# MCU_ADC.net
KiCad netlist of a schematic drawn in Altium Designer
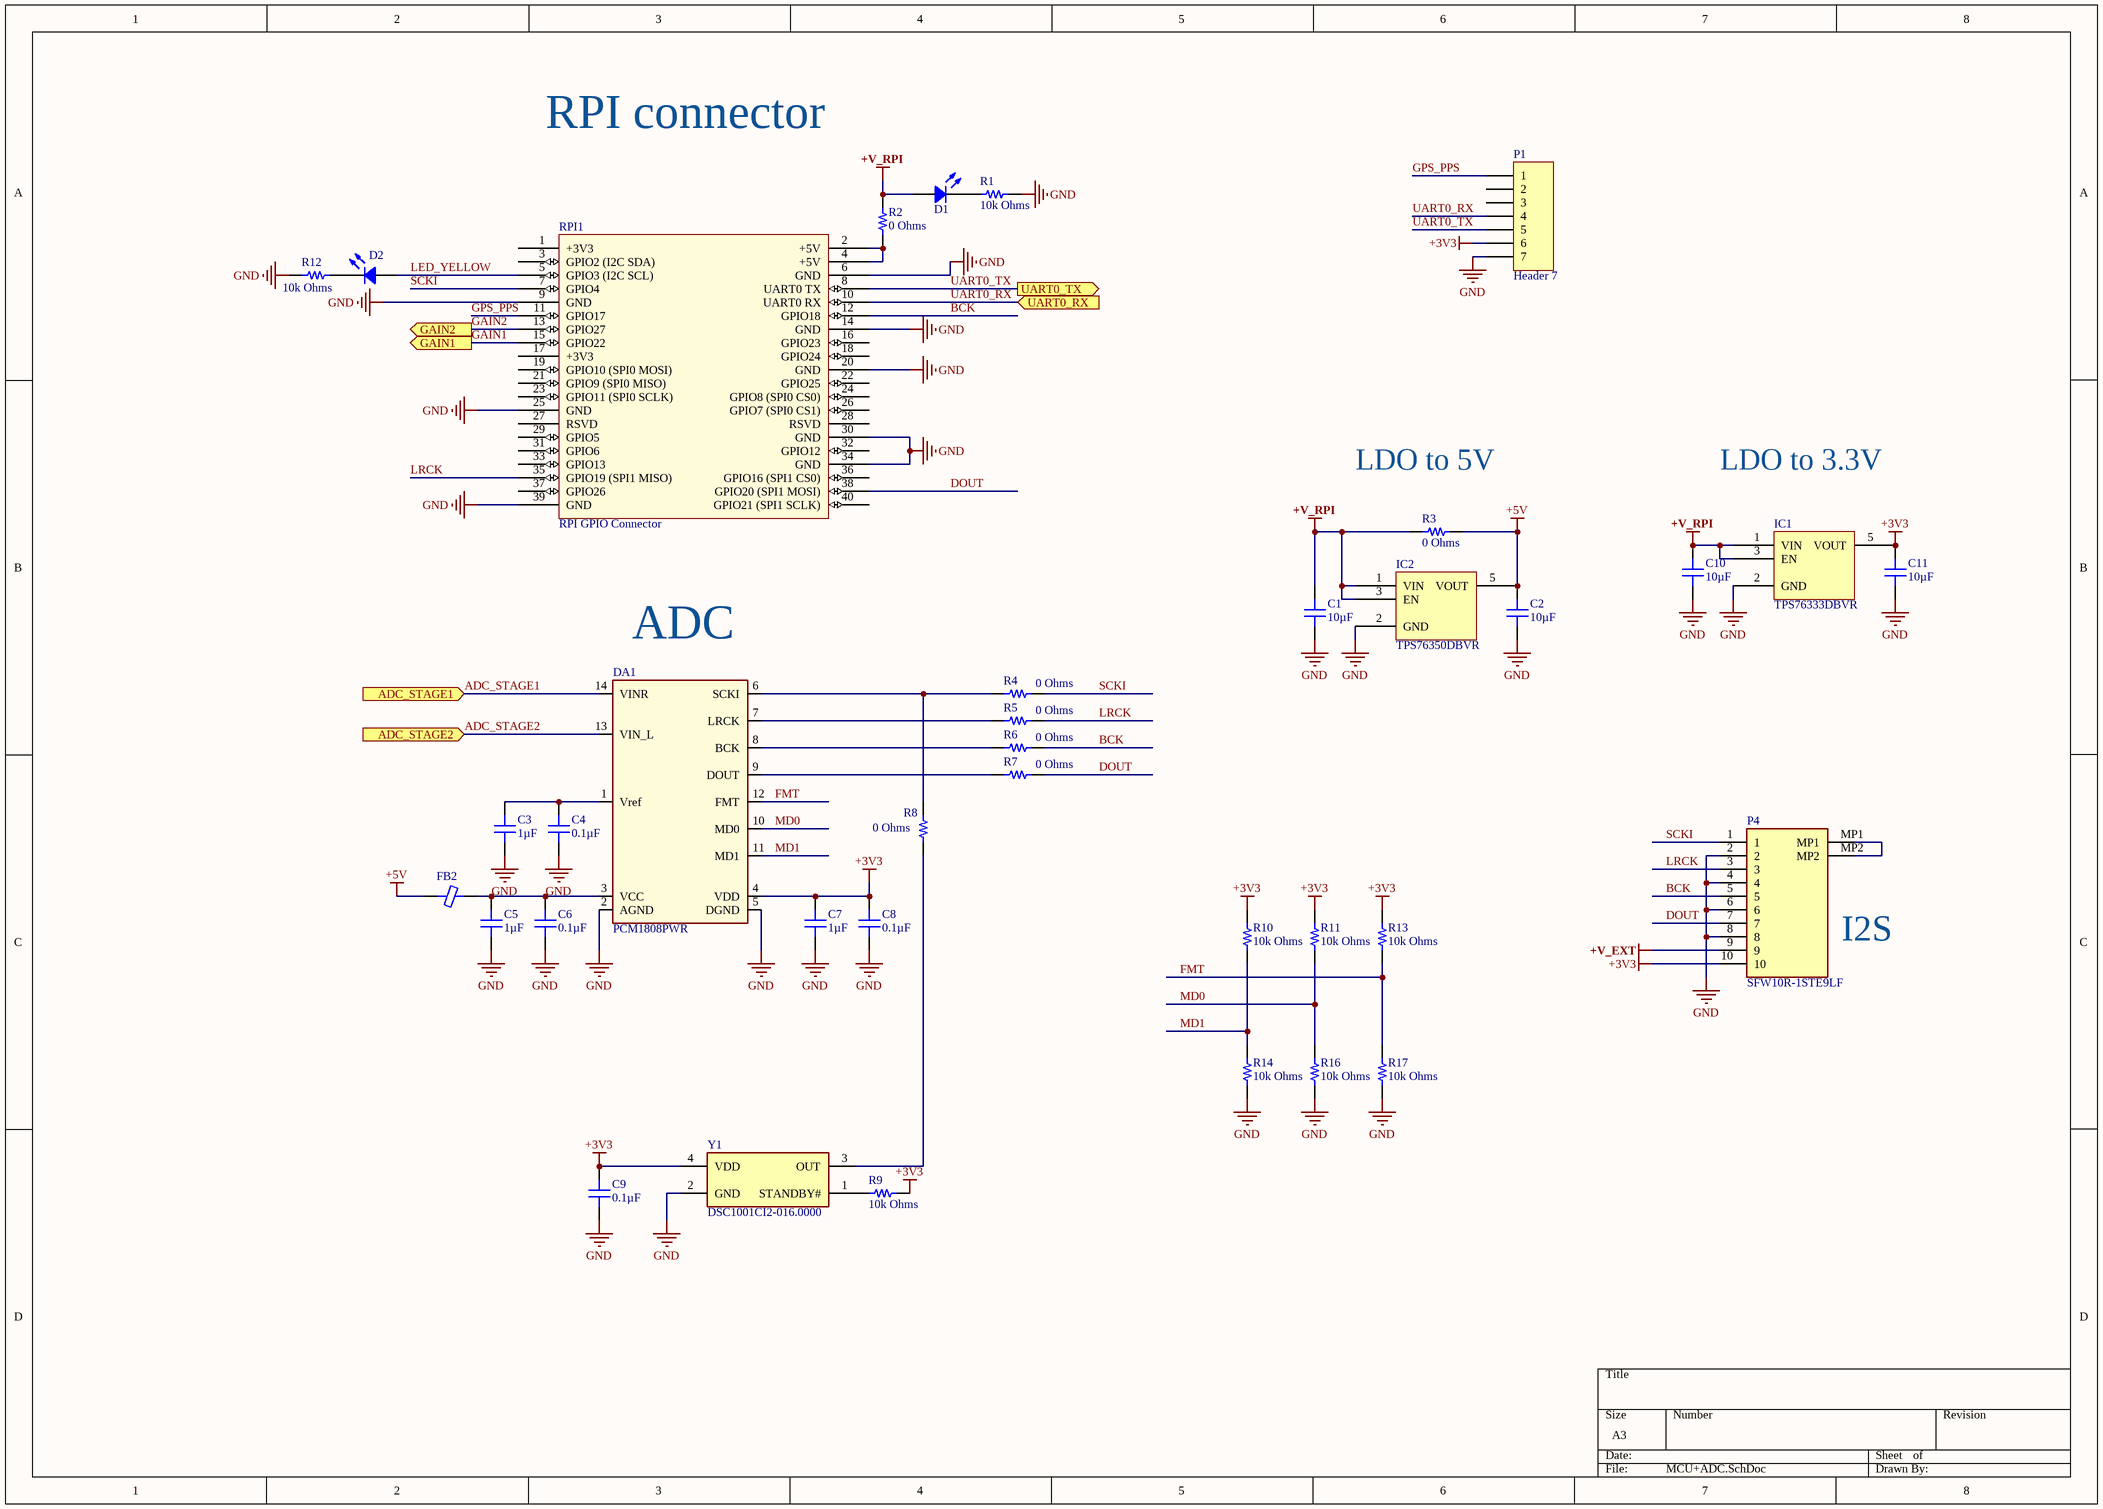
[diagram p0: MCU+ADC.SchDoc]

(export (version "E")
  (design (tool "Eeschema 10.0.6"))
  (components
    (comp (ref "C1")
      (value "10µF")
      (footprint "CAP 0603_1608")
      (description "CAP CER 0.1UF 10V X7R 0603")
      (fields (field (name "PART NUMBER") "100X14W104MV4T"))
      (libsource (lib "Celestial Altium Library - altium_library") (part "Capacitor"))
    )
    (comp (ref "C2")
      (value "10µF")
      (footprint "CAP 0603_1608")
      (description "CAP CER 0.1UF 10V X7R 0603")
      (fields (field (name "PART NUMBER") "100X14W104MV4T"))
      (libsource (lib "Celestial Altium Library - altium_library") (part "Capacitor"))
    )
    (comp (ref "C3")
      (value "1µF")
      (footprint "CAP 0603_1608")
      (description "CAP CER 0.1UF 10V X7R 0603")
      (fields (field (name "PART NUMBER") "100X14W104MV4T"))
      (libsource (lib "Celestial Altium Library - altium_library") (part "Capacitor"))
    )
    (comp (ref "C4")
      (value "0.1µF")
      (footprint "CAP 0603_1608")
      (description "CAP CER 0.1UF 10V X7R 0603")
      (fields (field (name "PART NUMBER") "100X14W104MV4T"))
      (libsource (lib "Celestial Altium Library - altium_library") (part "Capacitor"))
    )
    (comp (ref "C5")
      (value "1µF")
      (footprint "CAP 0603_1608")
      (description "CAP CER 0.1UF 10V X7R 0603")
      (fields (field (name "PART NUMBER") "100X14W104MV4T"))
      (libsource (lib "Celestial Altium Library - altium_library") (part "Capacitor"))
    )
    (comp (ref "C6")
      (value "0.1µF")
      (footprint "CAP 0603_1608")
      (description "CAP CER 0.1UF 10V X7R 0603")
      (fields (field (name "PART NUMBER") "100X14W104MV4T"))
      (libsource (lib "Celestial Altium Library - altium_library") (part "Capacitor"))
    )
    (comp (ref "C7")
      (value "1µF")
      (footprint "CAP 0603_1608")
      (description "CAP CER 0.1UF 10V X7R 0603")
      (fields (field (name "PART NUMBER") "100X14W104MV4T"))
      (libsource (lib "Celestial Altium Library - altium_library") (part "Capacitor"))
    )
    (comp (ref "C8")
      (value "0.1µF")
      (footprint "CAP 0603_1608")
      (description "CAP CER 0.1UF 10V X7R 0603")
      (fields (field (name "PART NUMBER") "100X14W104MV4T"))
      (libsource (lib "Celestial Altium Library - altium_library") (part "Capacitor"))
    )
    (comp (ref "C9")
      (value "0.1µF")
      (footprint "CAP 0603_1608")
      (description "CAP CER 0.1UF 10V X7R 0603")
      (fields (field (name "PART NUMBER") "100X14W104MV4T"))
      (libsource (lib "Celestial Altium Library - altium_library") (part "Capacitor"))
    )
    (comp (ref "C10")
      (value "10µF")
      (footprint "CAP 0603_1608")
      (description "CAP CER 0.1UF 10V X7R 0603")
      (fields (field (name "PART NUMBER") "100X14W104MV4T"))
      (libsource (lib "Celestial Altium Library - altium_library") (part "Capacitor"))
    )
    (comp (ref "C11")
      (value "10µF")
      (footprint "CAP 0603_1608")
      (description "CAP CER 0.1UF 10V X7R 0603")
      (fields (field (name "PART NUMBER") "100X14W104MV4T"))
      (libsource (lib "Celestial Altium Library - altium_library") (part "Capacitor"))
    )
    (comp (ref "D1")
      (value "~")
      (footprint "LED 0603_1608 RED")
      (description "LED RED 0603 SMD")
      (fields (field (name "PART NUMBER") "5973005507F"))
      (libsource (lib "Celestial Altium Library - altium_library") (part "LED"))
    )
    (comp (ref "D2")
      (value "~")
      (footprint "LED 0603_1608 YELLOW")
      (description "LED YELLOW 0603 SMD")
      (fields (field (name "PART NUMBER") "5973408507F"))
      (libsource (lib "Celestial Altium Library - altium_library") (part "LED"))
    )
    (comp (ref "DA1")
      (value "PCM1808PWR")
      (footprint "TSSOP 14")
      (description "Audio ADC, 24 bit, 192 kHz")
      (fields (field (name "MANUFACTURER") "Texas Instruments"))
      (libsource (lib "PCM1808 HPF _LMV791 v1.1") (part "PCM1808PWR"))
    )
    (comp (ref "FB2")
      (value "~")
      (footprint "FER 0603_1608")
      (description "FERRITE BEAD 0603 1LN")
      (fields (field (name "PART NUMBER") "2506031217H0"))
      (libsource (lib "Celestial Altium Library - altium_library") (part "Ferrite Chip"))
    )
    (comp (ref "IC1")
      (value "TPS76333DBVR")
      (footprint "TI SOT-23-5 DBV")
      (description "IC REG LINEAR 3.3V 150MA SOT23-5")
      (libsource (lib "Celestial Altium Library - altium_library") (part "TI TPS763xx"))
    )
    (comp (ref "IC2")
      (value "TPS76350DBVR")
      (footprint "TI SOT-23-5 DBV")
      (description "IC REG LINEAR 5V 150MA SOT23-5")
      (fields (field (name "MANUFACTURER") "Texas Instruments"))
      (libsource (lib "Celestial Altium Library - altium_library") (part "TI TPS763xx"))
    )
    (comp (ref "P1")
      (value "Header 7")
      (footprint "HDR1X7")
      (description "Header, 7-Pin")
      (fields (field (name "PUBLISHER") "Altium Limited"))
      (libsource (lib "Miscellaneous Connectors") (part "Header 7"))
    )
    (comp (ref "P4")
      (value "SFW10R-1STE9LF")
      (footprint "SamacSys:SFW10R1STE9LF")
      (description "Connector")
      (fields (field (name "MOUSER PART NUMBER") "649-SFW10R-1STE9LF"))
      (libsource (lib "*") (part "SFW10R-1STE9LF"))
    )
    (comp (ref "R1")
      (value "10k Ohms")
      (footprint "RES 0603_1608")
      (description "RES 100 OHM 0.1% 1/16W 0603")
      (fields (field (name "PART NUMBER") "RNCS0603BKE100R"))
      (libsource (lib "Celestial Altium Library - altium_library") (part "Resistor"))
    )
    (comp (ref "R2")
      (value "0 Ohms")
      (footprint "RES 1206_3216")
      (description "1206 SIZE, 0.25W, 350 OHM, 0.01%")
      (fields (field (name "PART NUMBER") "URG3216L-3500-L-T05") (field (name "MANUFACTURER") "Susumu"))
      (libsource (lib "Celestial Altium Library - altium_library") (part "Resistor"))
    )
    (comp (ref "R3")
      (value "0 Ohms")
      (footprint "RES 0603_1608")
      (description "RES 100 OHM 0.1% 1/16W 0603")
      (fields (field (name "PART NUMBER") "RNCS0603BKE100R"))
      (libsource (lib "Celestial Altium Library - altium_library") (part "Resistor"))
    )
    (comp (ref "R4")
      (value "0 Ohms")
      (footprint "RES 0603_1608")
      (description "RES 100 OHM 0.1% 1/16W 0603")
      (fields (field (name "PART NUMBER") "RNCS0603BKE100R"))
      (libsource (lib "Celestial Altium Library - altium_library") (part "Resistor"))
    )
    (comp (ref "R5")
      (value "0 Ohms")
      (footprint "RES 0603_1608")
      (description "RES 100 OHM 0.1% 1/16W 0603")
      (fields (field (name "PART NUMBER") "RNCS0603BKE100R"))
      (libsource (lib "Celestial Altium Library - altium_library") (part "Resistor"))
    )
    (comp (ref "R6")
      (value "0 Ohms")
      (footprint "RES 0603_1608")
      (description "RES 100 OHM 0.1% 1/16W 0603")
      (fields (field (name "PART NUMBER") "RNCS0603BKE100R"))
      (libsource (lib "Celestial Altium Library - altium_library") (part "Resistor"))
    )
    (comp (ref "R7")
      (value "0 Ohms")
      (footprint "RES 0603_1608")
      (description "RES 100 OHM 0.1% 1/16W 0603")
      (fields (field (name "PART NUMBER") "RNCS0603BKE100R"))
      (libsource (lib "Celestial Altium Library - altium_library") (part "Resistor"))
    )
    (comp (ref "R8")
      (value "0 Ohms")
      (footprint "RES 0603_1608")
      (description "RES 100 OHM 0.1% 1/16W 0603")
      (fields (field (name "PART NUMBER") "RNCS0603BKE100R"))
      (libsource (lib "Celestial Altium Library - altium_library") (part "Resistor"))
    )
    (comp (ref "R9")
      (value "10k Ohms")
      (footprint "RES 0603_1608")
      (description "RES 100 OHM 0.1% 1/16W 0603")
      (fields (field (name "PART NUMBER") "RNCS0603BKE100R"))
      (libsource (lib "Celestial Altium Library - altium_library") (part "Resistor"))
    )
    (comp (ref "R10")
      (value "10k Ohms")
      (footprint "RES 0603_1608")
      (description "RES 100 OHM 0.1% 1/16W 0603")
      (fields (field (name "PART NUMBER") "RNCS0603BKE100R"))
      (libsource (lib "Celestial Altium Library - altium_library") (part "Resistor"))
    )
    (comp (ref "R11")
      (value "10k Ohms")
      (footprint "RES 0603_1608")
      (description "RES 100 OHM 0.1% 1/16W 0603")
      (fields (field (name "PART NUMBER") "RNCS0603BKE100R"))
      (libsource (lib "Celestial Altium Library - altium_library") (part "Resistor"))
    )
    (comp (ref "R12")
      (value "10k Ohms")
      (footprint "RES 0603_1608")
      (description "RES 100 OHM 0.1% 1/16W 0603")
      (fields (field (name "PART NUMBER") "RNCS0603BKE100R"))
      (libsource (lib "Celestial Altium Library - altium_library") (part "Resistor"))
    )
    (comp (ref "R13")
      (value "10k Ohms")
      (footprint "RES 0603_1608")
      (description "RES 100 OHM 0.1% 1/16W 0603")
      (fields (field (name "PART NUMBER") "RNCS0603BKE100R"))
      (libsource (lib "Celestial Altium Library - altium_library") (part "Resistor"))
    )
    (comp (ref "R14")
      (value "10k Ohms")
      (footprint "RES 0603_1608")
      (description "RES 100 OHM 0.1% 1/16W 0603")
      (fields (field (name "PART NUMBER") "RNCS0603BKE100R"))
      (libsource (lib "Celestial Altium Library - altium_library") (part "Resistor"))
    )
    (comp (ref "R16")
      (value "10k Ohms")
      (footprint "RES 0603_1608")
      (description "RES 100 OHM 0.1% 1/16W 0603")
      (fields (field (name "PART NUMBER") "RNCS0603BKE100R"))
      (libsource (lib "Celestial Altium Library - altium_library") (part "Resistor"))
    )
    (comp (ref "R17")
      (value "10k Ohms")
      (footprint "RES 0603_1608")
      (description "RES 100 OHM 0.1% 1/16W 0603")
      (fields (field (name "PART NUMBER") "RNCS0603BKE100R"))
      (libsource (lib "Celestial Altium Library - altium_library") (part "Resistor"))
    )
    (comp (ref "RPI1")
      (value "RPI GPIO Connector")
      (footprint "rpi")
      (description "GPIO Header for Raspberry Pi A+/B+/Pi 2/Pi 3 - 2x20")
      (fields
        (field (name "MANUFACTURER") "SparkFun Electronics")
        (field (name "MANUFACTURER PART NUMBER") "PRT-14017")
      )
      (libsource (lib "RPI shield") (part "rpi connector"))
    )
    (comp (ref "Y1")
      (value "DSC1001CI2-016.0000")
      (footprint "DSC1001CI20160000")
      (description "Crystal or Oscillator")
      (libsource (lib "SamacSys") (part "DSC1001CI2-016.0000"))
    )
  )
  (nets
    (net (code "1") (name "+3V3") (class "Default")
      (node (ref "C11") (pin "2") (pinfunction "2_2") (pintype "passive"))
      (node (ref "C7") (pin "2") (pinfunction "2_2") (pintype "passive"))
      (node (ref "C8") (pin "2") (pinfunction "2_2") (pintype "passive"))
      (node (ref "C9") (pin "2") (pinfunction "2_2") (pintype "passive"))
      (node (ref "DA1") (pin "4") (pinfunction "VDD_4") (pintype "passive"))
      (node (ref "IC1") (pin "5") (pinfunction "VOUT_5") (pintype "passive"))
      (node (ref "P1") (pin "6") (pinfunction "6_6") (pintype "passive"))
      (node (ref "P4") (pin "10") (pinfunction "10_10") (pintype "passive"))
      (node (ref "R10") (pin "1") (pinfunction "1_1") (pintype "passive"))
      (node (ref "R11") (pin "1") (pinfunction "1_1") (pintype "passive"))
      (node (ref "R13") (pin "1") (pinfunction "1_1") (pintype "passive"))
      (node (ref "R9") (pin "1") (pinfunction "1_1") (pintype "passive"))
      (node (ref "Y1") (pin "4") (pinfunction "VDD_4") (pintype "passive"))
    )
    (net (code "2") (name "+5V") (class "Default")
      (node (ref "C2") (pin "2") (pinfunction "2_2") (pintype "passive"))
      (node (ref "FB2") (pin "1") (pinfunction "1_1") (pintype "passive"))
      (node (ref "IC2") (pin "5") (pinfunction "VOUT_5") (pintype "passive"))
      (node (ref "R3") (pin "1") (pinfunction "1_1") (pintype "passive"))
    )
    (net (code "3") (name "+V_EXT") (class "Default")
      (node (ref "P4") (pin "9") (pinfunction "9_9") (pintype "passive"))
    )
    (net (code "4") (name "+V_RPI") (class "Default")
      (node (ref "C1") (pin "2") (pinfunction "2_2") (pintype "passive"))
      (node (ref "C10") (pin "2") (pinfunction "2_2") (pintype "passive"))
      (node (ref "D1") (pin "1") (pinfunction "1_1") (pintype "passive"))
      (node (ref "IC1") (pin "1") (pinfunction "VIN_1") (pintype "passive"))
      (node (ref "IC1") (pin "3") (pinfunction "EN_3") (pintype "passive"))
      (node (ref "IC2") (pin "1") (pinfunction "VIN_1") (pintype "passive"))
      (node (ref "IC2") (pin "3") (pinfunction "EN_3") (pintype "passive"))
      (node (ref "R2") (pin "2") (pinfunction "2_2") (pintype "passive"))
      (node (ref "R3") (pin "2") (pinfunction "2_2") (pintype "passive"))
    )
    (net (code "5") (name "/ADC_STAGE1") (class "Default")
      (node (ref "DA1") (pin "14") (pinfunction "VINR_14") (pintype "passive"))
    )
    (net (code "6") (name "/ADC_STAGE2") (class "Default")
      (node (ref "DA1") (pin "13") (pinfunction "VIN_L_13") (pintype "passive"))
    )
    (net (code "7") (name "/BCK") (class "Default")
      (node (ref "P4") (pin "5") (pinfunction "5_5") (pintype "passive"))
      (node (ref "R6") (pin "1") (pinfunction "1_1") (pintype "passive"))
      (node (ref "RPI1") (pin "12") (pinfunction "GPIO18_12") (pintype "bidirectional"))
    )
    (net (code "8") (name "/DOUT") (class "Default")
      (node (ref "P4") (pin "7") (pinfunction "7_7") (pintype "passive"))
      (node (ref "R7") (pin "1") (pinfunction "1_1") (pintype "passive"))
      (node (ref "RPI1") (pin "38") (pinfunction "GPIO20_(SPI1_MOSI)_38") (pintype "bidirectional"))
    )
    (net (code "9") (name "/FMT") (class "Default")
      (node (ref "DA1") (pin "12") (pinfunction "FMT_12") (pintype "passive"))
      (node (ref "R13") (pin "2") (pinfunction "2_2") (pintype "passive"))
      (node (ref "R17") (pin "1") (pinfunction "1_1") (pintype "passive"))
    )
    (net (code "10") (name "/GAIN1") (class "Default")
      (node (ref "RPI1") (pin "15") (pinfunction "GPIO22_15") (pintype "bidirectional"))
    )
    (net (code "11") (name "/GAIN2") (class "Default")
      (node (ref "RPI1") (pin "13") (pinfunction "GPIO27_13") (pintype "bidirectional"))
    )
    (net (code "12") (name "/GPS_PPS") (class "Default")
      (node (ref "P1") (pin "1") (pinfunction "1_1") (pintype "passive"))
      (node (ref "RPI1") (pin "11") (pinfunction "GPIO17_11") (pintype "bidirectional"))
    )
    (net (code "13") (name "/LED_YELLOW") (class "Default")
      (node (ref "D2") (pin "1") (pinfunction "1_1") (pintype "passive"))
      (node (ref "RPI1") (pin "5") (pinfunction "GPIO3_(I2C_SCL)_5") (pintype "bidirectional"))
    )
    (net (code "14") (name "/LRCK") (class "Default")
      (node (ref "P4") (pin "3") (pinfunction "3_3") (pintype "passive"))
      (node (ref "R5") (pin "1") (pinfunction "1_1") (pintype "passive"))
      (node (ref "RPI1") (pin "35") (pinfunction "GPIO19_(SPI1_MISO)_35") (pintype "bidirectional"))
    )
    (net (code "15") (name "/MD0") (class "Default")
      (node (ref "DA1") (pin "10") (pinfunction "MD0_10") (pintype "passive"))
      (node (ref "R11") (pin "2") (pinfunction "2_2") (pintype "passive"))
      (node (ref "R16") (pin "1") (pinfunction "1_1") (pintype "passive"))
    )
    (net (code "16") (name "/MD1") (class "Default")
      (node (ref "DA1") (pin "11") (pinfunction "MD1_11") (pintype "passive"))
      (node (ref "R10") (pin "2") (pinfunction "2_2") (pintype "passive"))
      (node (ref "R14") (pin "1") (pinfunction "1_1") (pintype "passive"))
    )
    (net (code "17") (name "/SCKI") (class "Default")
      (node (ref "P4") (pin "1") (pinfunction "1_1") (pintype "passive"))
      (node (ref "R4") (pin "1") (pinfunction "1_1") (pintype "passive"))
      (node (ref "RPI1") (pin "7") (pinfunction "GPIO4_7") (pintype "bidirectional"))
    )
    (net (code "18") (name "/UART0_RX") (class "Default")
      (node (ref "P1") (pin "4") (pinfunction "4_4") (pintype "passive"))
      (node (ref "RPI1") (pin "10") (pinfunction "UART0_RX_10") (pintype "bidirectional"))
    )
    (net (code "19") (name "/UART0_TX") (class "Default")
      (node (ref "P1") (pin "5") (pinfunction "5_5") (pintype "passive"))
      (node (ref "RPI1") (pin "8") (pinfunction "UART0_TX_8") (pintype "bidirectional"))
    )
    (net (code "20") (name "GND") (class "Default")
      (node (ref "C1") (pin "1") (pinfunction "1_1") (pintype "passive"))
      (node (ref "C10") (pin "1") (pinfunction "1_1") (pintype "passive"))
      (node (ref "C11") (pin "1") (pinfunction "1_1") (pintype "passive"))
      (node (ref "C2") (pin "1") (pinfunction "1_1") (pintype "passive"))
      (node (ref "C3") (pin "1") (pinfunction "1_1") (pintype "passive"))
      (node (ref "C4") (pin "1") (pinfunction "1_1") (pintype "passive"))
      (node (ref "C5") (pin "1") (pinfunction "1_1") (pintype "passive"))
      (node (ref "C6") (pin "1") (pinfunction "1_1") (pintype "passive"))
      (node (ref "C7") (pin "1") (pinfunction "1_1") (pintype "passive"))
      (node (ref "C8") (pin "1") (pinfunction "1_1") (pintype "passive"))
      (node (ref "C9") (pin "1") (pinfunction "1_1") (pintype "passive"))
      (node (ref "DA1") (pin "2") (pinfunction "AGND_2") (pintype "passive"))
      (node (ref "DA1") (pin "5") (pinfunction "DGND_5") (pintype "passive"))
      (node (ref "IC1") (pin "2") (pinfunction "GND_2") (pintype "passive"))
      (node (ref "IC2") (pin "2") (pinfunction "GND_2") (pintype "passive"))
      (node (ref "P1") (pin "7") (pinfunction "7_7") (pintype "passive"))
      (node (ref "P4") (pin "2") (pinfunction "2_2") (pintype "passive"))
      (node (ref "P4") (pin "4") (pinfunction "4_4") (pintype "passive"))
      (node (ref "P4") (pin "6") (pinfunction "6_6") (pintype "passive"))
      (node (ref "P4") (pin "8") (pinfunction "8_8") (pintype "passive"))
      (node (ref "R1") (pin "1") (pinfunction "1_1") (pintype "passive"))
      (node (ref "R12") (pin "1") (pinfunction "1_1") (pintype "passive"))
      (node (ref "R14") (pin "2") (pinfunction "2_2") (pintype "passive"))
      (node (ref "R16") (pin "2") (pinfunction "2_2") (pintype "passive"))
      (node (ref "R17") (pin "2") (pinfunction "2_2") (pintype "passive"))
      (node (ref "RPI1") (pin "14") (pinfunction "GND_14") (pintype "power_in"))
      (node (ref "RPI1") (pin "20") (pinfunction "GND_20") (pintype "power_in"))
      (node (ref "RPI1") (pin "25") (pinfunction "GND_25") (pintype "power_in"))
      (node (ref "RPI1") (pin "30") (pinfunction "GND_30") (pintype "power_in"))
      (node (ref "RPI1") (pin "34") (pinfunction "GND_34") (pintype "passive"))
      (node (ref "RPI1") (pin "39") (pinfunction "GND_39") (pintype "power_in"))
      (node (ref "RPI1") (pin "6") (pinfunction "GND_6") (pintype "power_in"))
      (node (ref "RPI1") (pin "9") (pinfunction "GND_9") (pintype "power_in"))
      (node (ref "Y1") (pin "2") (pinfunction "GND_2") (pintype "passive"))
    )
    (net (code "21") (name "Net-(D1-Pad2)") (class "Default")
      (node (ref "D1") (pin "2") (pinfunction "2_2") (pintype "passive"))
      (node (ref "R1") (pin "2") (pinfunction "2_2") (pintype "passive"))
    )
    (net (code "22") (name "Net-(D2-Pad2)") (class "Default")
      (node (ref "D2") (pin "2") (pinfunction "2_2") (pintype "passive"))
      (node (ref "R12") (pin "2") (pinfunction "2_2") (pintype "passive"))
    )
    (net (code "23") (name "Net-(DA1-BCK)") (class "Default")
      (node (ref "DA1") (pin "8") (pinfunction "BCK_8") (pintype "passive"))
      (node (ref "R6") (pin "2") (pinfunction "2_2") (pintype "passive"))
    )
    (net (code "24") (name "Net-(DA1-DOUT)") (class "Default")
      (node (ref "DA1") (pin "9") (pinfunction "DOUT_9") (pintype "passive"))
      (node (ref "R7") (pin "2") (pinfunction "2_2") (pintype "passive"))
    )
    (net (code "25") (name "Net-(DA1-LRCK)") (class "Default")
      (node (ref "DA1") (pin "7") (pinfunction "LRCK_7") (pintype "passive"))
      (node (ref "R5") (pin "2") (pinfunction "2_2") (pintype "passive"))
    )
    (net (code "26") (name "Net-(DA1-SCKI)") (class "Default")
      (node (ref "DA1") (pin "6") (pinfunction "SCKI_6") (pintype "passive"))
      (node (ref "R4") (pin "2") (pinfunction "2_2") (pintype "passive"))
      (node (ref "R8") (pin "1") (pinfunction "1_1") (pintype "passive"))
    )
    (net (code "27") (name "Net-(DA1-VCC)") (class "Default")
      (node (ref "C5") (pin "2") (pinfunction "2_2") (pintype "passive"))
      (node (ref "C6") (pin "2") (pinfunction "2_2") (pintype "passive"))
      (node (ref "DA1") (pin "3") (pinfunction "VCC_3") (pintype "passive"))
      (node (ref "FB2") (pin "2") (pinfunction "2_2") (pintype "passive"))
    )
    (net (code "28") (name "Net-(DA1-Vref)") (class "Default")
      (node (ref "C3") (pin "2") (pinfunction "2_2") (pintype "passive"))
      (node (ref "C4") (pin "2") (pinfunction "2_2") (pintype "passive"))
      (node (ref "DA1") (pin "1") (pinfunction "Vref_1") (pintype "passive"))
    )
    (net (code "29") (name "Net-(P4-PadMP1)") (class "Default")
      (node (ref "P4") (pin "MP1") (pinfunction "MP1_MP1") (pintype "passive"))
      (node (ref "P4") (pin "MP2") (pinfunction "MP2_MP2") (pintype "passive"))
    )
    (net (code "30") (name "Net-(R2-Pad1)") (class "Default")
      (node (ref "R2") (pin "1") (pinfunction "1_1") (pintype "passive"))
      (node (ref "RPI1") (pin "2") (pinfunction "+5V_2") (pintype "power_in"))
      (node (ref "RPI1") (pin "4") (pinfunction "+5V_4") (pintype "power_in"))
    )
    (net (code "31") (name "Net-(Y1-OUT)") (class "Default")
      (node (ref "R8") (pin "2") (pinfunction "2_2") (pintype "passive"))
      (node (ref "Y1") (pin "3") (pinfunction "OUT_3") (pintype "passive"))
    )
    (net (code "32") (name "Net-(Y1-STANDBY#)") (class "Default")
      (node (ref "R9") (pin "2") (pinfunction "2_2") (pintype "passive"))
      (node (ref "Y1") (pin "1") (pinfunction "STANDBY#_1") (pintype "passive"))
    )
    (net (code "33") (name "unconnected-(P1-Pad2)") (class "Default")
      (node (ref "P1") (pin "2") (pinfunction "2_2") (pintype "passive"))
    )
    (net (code "34") (name "unconnected-(P1-Pad3)") (class "Default")
      (node (ref "P1") (pin "3") (pinfunction "3_3") (pintype "passive"))
    )
    (net (code "35") (name "unconnected-(RPI1-+3V3-Pad1)") (class "Default")
      (node (ref "RPI1") (pin "1") (pinfunction "+3V3_1") (pintype "power_in"))
    )
    (net (code "36") (name "unconnected-(RPI1-+3V3-Pad17)") (class "Default")
      (node (ref "RPI1") (pin "17") (pinfunction "+3V3_17") (pintype "power_in"))
    )
    (net (code "37") (name "unconnected-(RPI1-GPIO2_(I2C_SDA)-Pad3)") (class "Default")
      (node (ref "RPI1") (pin "3") (pinfunction "GPIO2_(I2C_SDA)_3") (pintype "bidirectional"))
    )
    (net (code "38") (name "unconnected-(RPI1-GPIO5-Pad29)") (class "Default")
      (node (ref "RPI1") (pin "29") (pinfunction "GPIO5_29") (pintype "bidirectional"))
    )
    (net (code "39") (name "unconnected-(RPI1-GPIO6-Pad31)") (class "Default")
      (node (ref "RPI1") (pin "31") (pinfunction "GPIO6_31") (pintype "bidirectional"))
    )
    (net (code "40") (name "unconnected-(RPI1-GPIO7_(SPI0_CS1)-Pad26)") (class "Default")
      (node (ref "RPI1") (pin "26") (pinfunction "GPIO7_(SPI0_CS1)_26") (pintype "bidirectional"))
    )
    (net (code "41") (name "unconnected-(RPI1-GPIO8_(SPI0_CS0)-Pad24)") (class "Default")
      (node (ref "RPI1") (pin "24") (pinfunction "GPIO8_(SPI0_CS0)_24") (pintype "bidirectional"))
    )
    (net (code "42") (name "unconnected-(RPI1-GPIO9_(SPI0_MISO)-Pad21)") (class "Default")
      (node (ref "RPI1") (pin "21") (pinfunction "GPIO9_(SPI0_MISO)_21") (pintype "bidirectional"))
    )
    (net (code "43") (name "unconnected-(RPI1-GPIO10_(SPI0_MOSI)-Pad19)") (class "Default")
      (node (ref "RPI1") (pin "19") (pinfunction "GPIO10_(SPI0_MOSI)_19") (pintype "bidirectional"))
    )
    (net (code "44") (name "unconnected-(RPI1-GPIO11_(SPI0_SCLK)-Pad23)") (class "Default")
      (node (ref "RPI1") (pin "23") (pinfunction "GPIO11_(SPI0_SCLK)_23") (pintype "bidirectional"))
    )
    (net (code "45") (name "unconnected-(RPI1-GPIO12-Pad32)") (class "Default")
      (node (ref "RPI1") (pin "32") (pinfunction "GPIO12_32") (pintype "bidirectional"))
    )
    (net (code "46") (name "unconnected-(RPI1-GPIO13-Pad33)") (class "Default")
      (node (ref "RPI1") (pin "33") (pinfunction "GPIO13_33") (pintype "bidirectional"))
    )
    (net (code "47") (name "unconnected-(RPI1-GPIO16_(SPI1_CS0)-Pad36)") (class "Default")
      (node (ref "RPI1") (pin "36") (pinfunction "GPIO16_(SPI1_CS0)_36") (pintype "bidirectional"))
    )
    (net (code "48") (name "unconnected-(RPI1-GPIO21_(SPI1_SCLK)-Pad40)") (class "Default")
      (node (ref "RPI1") (pin "40") (pinfunction "GPIO21_(SPI1_SCLK)_40") (pintype "bidirectional"))
    )
    (net (code "49") (name "unconnected-(RPI1-GPIO23-Pad16)") (class "Default")
      (node (ref "RPI1") (pin "16") (pinfunction "GPIO23_16") (pintype "bidirectional"))
    )
    (net (code "50") (name "unconnected-(RPI1-GPIO24-Pad18)") (class "Default")
      (node (ref "RPI1") (pin "18") (pinfunction "GPIO24_18") (pintype "bidirectional"))
    )
    (net (code "51") (name "unconnected-(RPI1-GPIO25-Pad22)") (class "Default")
      (node (ref "RPI1") (pin "22") (pinfunction "GPIO25_22") (pintype "bidirectional"))
    )
    (net (code "52") (name "unconnected-(RPI1-GPIO26-Pad37)") (class "Default")
      (node (ref "RPI1") (pin "37") (pinfunction "GPIO26_37") (pintype "bidirectional"))
    )
    (net (code "53") (name "unconnected-(RPI1-RSVD-Pad27)") (class "Default")
      (node (ref "RPI1") (pin "27") (pinfunction "RSVD_27") (pintype "passive"))
    )
    (net (code "54") (name "unconnected-(RPI1-RSVD-Pad28)") (class "Default")
      (node (ref "RPI1") (pin "28") (pinfunction "RSVD_28") (pintype "passive"))
    )
  )
)
